# Tachometer.net
KiCad netlist of a schematic drawn in EAGLE
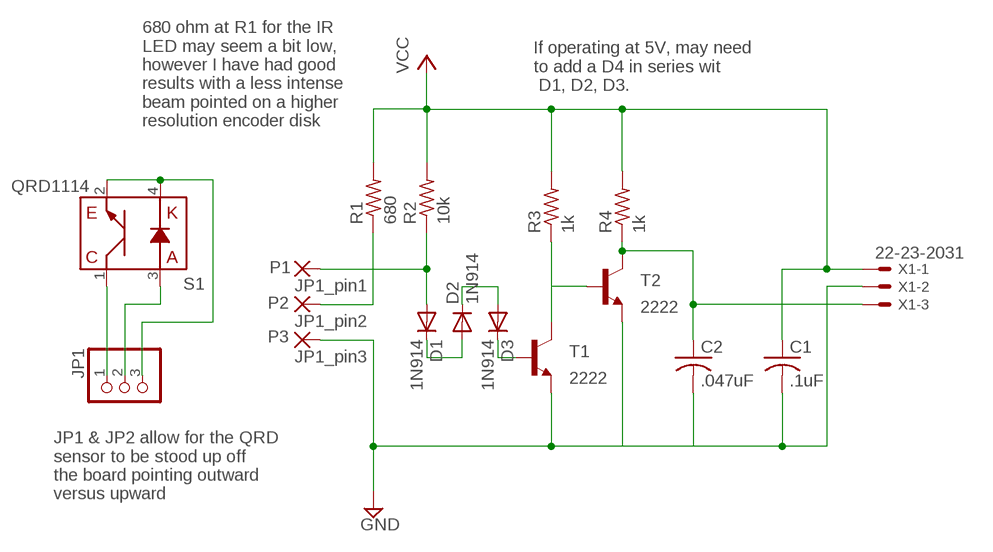
[diagram p0: schematic, sheet 1]

(export (version "E")
  (design (tool "Eeschema 10.0.6"))
  (components
    (comp (ref "C1")
      (value ".1uF")
      (footprint "eagle-import:C025-024X044")
      (libsource (lib "eagle-import") (part "C-US025-024X044"))
    )
    (comp (ref "C2")
      (value ".047uF")
      (footprint "eagle-import:C025-024X044")
      (libsource (lib "eagle-import") (part "C-US025-024X044"))
    )
    (comp (ref "D1")
      (value "1N914")
      (footprint "eagle-import:D-2.5")
      (libsource (lib "eagle-import") (part "DIODE-D-2.5"))
    )
    (comp (ref "D2")
      (value "1N914")
      (footprint "eagle-import:D-2.5")
      (libsource (lib "eagle-import") (part "DIODE-D-2.5"))
    )
    (comp (ref "D3")
      (value "1N914")
      (footprint "eagle-import:D-2.5")
      (libsource (lib "eagle-import") (part "DIODE-D-2.5"))
    )
    (comp (ref "JP1")
      (value "PINHD-1X3/90")
      (footprint "eagle-import:1X03_90")
      (libsource (lib "eagle-import") (part "PINHD-1X3/90"))
    )
    (comp (ref "P1")
      (value "JP1_pin1")
      (footprint "eagle-import:1,6_0,9")
      (libsource (lib "eagle-import") (part "1,6/0,9"))
    )
    (comp (ref "P2")
      (value "JP1_pin2")
      (footprint "eagle-import:1,6_0,9")
      (libsource (lib "eagle-import") (part "1,6/0,9"))
    )
    (comp (ref "P3")
      (value "JP1_pin3")
      (footprint "eagle-import:1,6_0,9")
      (libsource (lib "eagle-import") (part "1,6/0,9"))
    )
    (comp (ref "R1")
      (value "680")
      (footprint "eagle-import:0204_5")
      (libsource (lib "eagle-import") (part "R-US_0204/5"))
    )
    (comp (ref "R2")
      (value "10k")
      (footprint "eagle-import:0204_5")
      (libsource (lib "eagle-import") (part "R-US_0204/5"))
    )
    (comp (ref "R3")
      (value "1k")
      (footprint "eagle-import:0204_5")
      (libsource (lib "eagle-import") (part "R-US_0204/5"))
    )
    (comp (ref "R4")
      (value "1k")
      (footprint "eagle-import:0204_5")
      (libsource (lib "eagle-import") (part "R-US_0204/5"))
    )
    (comp (ref "S1")
      (value "QRD1114")
      (footprint "eagle-import:QRD1114")
      (libsource (lib "eagle-import") (part "QRD1114"))
    )
    (comp (ref "T1")
      (value "2222")
      (footprint "eagle-import:TO92-EBC")
      (libsource (lib "eagle-import") (part "-NPN-TO92-EBC"))
    )
    (comp (ref "T2")
      (value "2222")
      (footprint "eagle-import:TO92-EBC")
      (libsource (lib "eagle-import") (part "-NPN-TO92-EBC"))
    )
    (comp (ref "X1")
      (value "22-23-2031")
      (footprint "eagle-import:22-23-2031")
      (fields (field (name "MF") "MOLEX"))
      (libsource (lib "eagle-import") (part "22-23-2031"))
    )
  )
  (nets
    (net (code "1") (name "GND") (class "Default")
      (node (ref "C1") (pin "2") (pinfunction "2_2") (pintype "passive"))
      (node (ref "C2") (pin "2") (pinfunction "2_2") (pintype "passive"))
      (node (ref "P3") (pin "1") (pinfunction "P_1") (pintype "passive"))
      (node (ref "T1") (pin "E") (pinfunction "E_E") (pintype "passive"))
      (node (ref "T2") (pin "E") (pinfunction "E_E") (pintype "passive"))
      (node (ref "X1") (pin "2") (pinfunction "S_2") (pintype "passive"))
    )
    (net (code "2") (name "Net-(D1-PadC)") (class "Default")
      (node (ref "D1") (pin "C") (pinfunction "C_C") (pintype "passive"))
      (node (ref "D2") (pin "A") (pinfunction "A_A") (pintype "passive"))
    )
    (net (code "3") (name "Net-(D2-PadC)") (class "Default")
      (node (ref "D2") (pin "C") (pinfunction "C_C") (pintype "passive"))
      (node (ref "D3") (pin "A") (pinfunction "A_A") (pintype "passive"))
    )
    (net (code "4") (name "Net-(D3-PadC)") (class "Default")
      (node (ref "D3") (pin "C") (pinfunction "C_C") (pintype "passive"))
      (node (ref "T1") (pin "B") (pinfunction "B_B") (pintype "passive"))
    )
    (net (code "5") (name "Net-(P1-P)") (class "Default")
      (node (ref "D1") (pin "A") (pinfunction "A_A") (pintype "passive"))
      (node (ref "P1") (pin "1") (pinfunction "P_1") (pintype "passive"))
      (node (ref "R2") (pin "1") (pinfunction "1_1") (pintype "passive"))
    )
    (net (code "6") (name "Net-(P2-P)") (class "Default")
      (node (ref "P2") (pin "1") (pinfunction "P_1") (pintype "passive"))
      (node (ref "R1") (pin "1") (pinfunction "1_1") (pintype "passive"))
    )
    (net (code "7") (name "Net-(R3-Pad1)") (class "Default")
      (node (ref "R3") (pin "1") (pinfunction "1_1") (pintype "passive"))
      (node (ref "T1") (pin "C") (pinfunction "C_C") (pintype "passive"))
      (node (ref "T2") (pin "B") (pinfunction "B_B") (pintype "passive"))
    )
    (net (code "8") (name "Net-(S1-A)") (class "Default")
      (node (ref "JP1") (pin "2") (pinfunction "2_2") (pintype "passive"))
      (node (ref "S1") (pin "3") (pinfunction "A_3") (pintype "bidirectional"))
    )
    (net (code "9") (name "Net-(S1-C)") (class "Default")
      (node (ref "JP1") (pin "3") (pinfunction "3_3") (pintype "passive"))
      (node (ref "S1") (pin "2") (pinfunction "C_2") (pintype "bidirectional"))
      (node (ref "S1") (pin "4") (pinfunction "K_4") (pintype "bidirectional"))
    )
    (net (code "10") (name "Net-(S1-E)") (class "Default")
      (node (ref "JP1") (pin "1") (pinfunction "1_1") (pintype "passive"))
      (node (ref "S1") (pin "1") (pinfunction "E_1") (pintype "bidirectional"))
    )
    (net (code "11") (name "Net-(X1C-S)") (class "Default")
      (node (ref "C2") (pin "1") (pinfunction "1_1") (pintype "passive"))
      (node (ref "R4") (pin "1") (pinfunction "1_1") (pintype "passive"))
      (node (ref "T2") (pin "C") (pinfunction "C_C") (pintype "passive"))
      (node (ref "X1") (pin "3") (pinfunction "S_3") (pintype "passive"))
    )
    (net (code "12") (name "VCC") (class "Default")
      (node (ref "C1") (pin "1") (pinfunction "1_1") (pintype "passive"))
      (node (ref "R1") (pin "2") (pinfunction "2_2") (pintype "passive"))
      (node (ref "R2") (pin "2") (pinfunction "2_2") (pintype "passive"))
      (node (ref "R3") (pin "2") (pinfunction "2_2") (pintype "passive"))
      (node (ref "R4") (pin "2") (pinfunction "2_2") (pintype "passive"))
      (node (ref "X1") (pin "1") (pinfunction "S_1") (pintype "passive"))
    )
  )
)
